# Thunderbots.net
KiCad netlist of a schematic drawn in Altium Designer
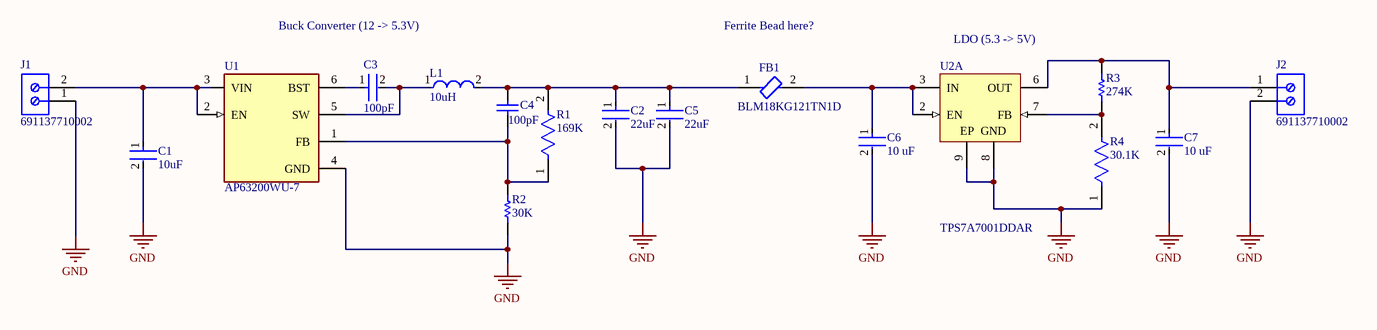
[diagram p0: Thunderbots.SchDoc]

(export (version "E")
  (design (tool "Eeschema 10.0.6"))
  (components
    (comp (ref "C1")
      (value "10uF")
      (footprint "FP-RDE3P1-MFG")
      (description "Ceramic Capacitor 10uF ±10% 50V X7S Radial")
      (fields (field (name "TOLERANCE") "10%"))
      (libsource (lib "Altium Content Vault") (part "02cd4be3c70576c341d710602a673aa"))
    )
    (comp (ref "C2")
      (value "22uF")
      (footprint "FP-RDEWK1-MFG")
      (description "CAP CER 22UF 50V X7S RADIAL")
      (fields (field (name "TOLERANCE") "20%"))
      (libsource (lib "Altium Content Vault") (part "02cd4be3c70576c341d710602a673aa"))
    )
    (comp (ref "C3")
      (value "100pF")
      (footprint "FP-C0402-BB-MFG")
      (description "C0402 0.10 μF X7R 10.00% 10 V")
      (fields (field (name "OCTOPART") "https://octopart.com/c0402c104k8ractu-kemet-106349"))
      (libsource (lib "Altium Content Vault") (part "b4654b650e69147ec39a6b967a45e02"))
    )
    (comp (ref "C4")
      (value "100pF")
      (footprint "CAPC2013X127X50NL20T25")
      (fields
        (field (name "PART NUMBER") "08052C101KAT2A")
        (field (name "MANUFACTURER") "AVX Interconnect / Elco")
      )
      (libsource (lib "Altium Content Vault") (part "CAP"))
    )
    (comp (ref "C5")
      (value "22uF")
      (footprint "FP-RDEWK1-MFG")
      (description "CAP CER 22UF 50V X7S RADIAL")
      (fields (field (name "TOLERANCE") "20%"))
      (libsource (lib "Altium Content Vault") (part "02cd4be3c70576c341d710602a673aa"))
    )
    (comp (ref "C6")
      (value "10 uF")
      (footprint "FP-RDE3P1-MFG")
      (description "Ceramic Capacitor 10uF ±10% 50V X7S Radial")
      (fields (field (name "TOLERANCE") "10%"))
      (libsource (lib "Altium Content Vault") (part "02cd4be3c70576c341d710602a673aa"))
    )
    (comp (ref "C7")
      (value "10 uF")
      (footprint "FP-CL05A106MP5NUNC-MFG")
      (description "CAP CER 10UF 10V X5R 0402")
      (fields
        (field (name "OCTOPART") "https://octopart.com/cl05a106mp5nunc-samsung-22457395")
        (field (name "TOLERANCE") "20%")
      )
      (libsource (lib "Altium Content Vault") (part "b4654b650e69147ec39a6b967a45e02"))
    )
    (comp (ref "FB1")
      (value "BLM18KG121TN1D")
      (footprint "FP-BLM18-0_15-t0_6-d1_2-IPC_A")
      (description "FERRITE BEAD 120 OHM 0603 1LN")
      (fields (field (name "TOLERANCE") "25%"))
      (libsource (lib "Altium Content Vault") (part "5f30dd21d616792df468990f7003faa"))
    )
    (comp (ref "J1")
      (value "691137710002")
      (footprint "691137710002")
      (libsource (lib "Altium Content Vault") (part "TBL - 1R - 02P - Screw"))
    )
    (comp (ref "J2")
      (value "691137710002")
      (footprint "691137710002")
      (libsource (lib "Altium Content Vault") (part "TBL - 1R - 02P - Screw"))
    )
    (comp (ref "L1")
      (value "10uH")
      (footprint "FP-NR6045-MFG")
      (description "Shielded Wirewound Inductor 10uH 20% 2.5A 61.1mΩ SMD")
      (fields (field (name "TOLERANCE") "20%"))
      (libsource (lib "Altium Content Vault") (part "725321dda6339637d4d059423bc1c3c"))
    )
    (comp (ref "R1")
      (value "169K")
      (footprint "FP-RMCF0603-IPC_A")
      (description "169kΩ ±1% 0.1W 0603 Thick Film Chip Resistor AEC-Q200 compliant")
      (fields (field (name "TOLERANCE") "1%"))
      (libsource (lib "Altium Content Vault") (part "1029c3af85768c4190bb7ad29bc67b5"))
    )
    (comp (ref "R2")
      (value "30K")
      (footprint "RESC1005X40X25LL05T05")
      (fields (field (name "PART NUMBER") "CRCW040230K0FKED") (field (name "MANUFACTURER") "Vishay Dale"))
      (libsource (lib "Altium Content Vault") (part "RES"))
    )
    (comp (ref "R3")
      (value "274K")
      (footprint "RESC1005X40X25ML05T05")
      (fields (field (name "MANUFACTURER") "Panasonic") (field (name "PART NUMBER") "ERJ-2RKF2743X"))
      (libsource (lib "Altium Content Vault") (part "RES"))
    )
    (comp (ref "R4")
      (value "30.1K")
      (footprint "FP-ERJ6EN-MFG")
      (fields (field (name "TOLERANCE") "1%"))
      (libsource (lib "Altium Content Vault") (part "1029c3af85768c4190bb7ad29bc67b5"))
    )
    (comp (ref "U1")
      (value "AP63200WU-7")
      (footprint "FP-TSOT26-MFG")
      (description "IC REG BUCK ADJUSTABLE 2A TSOT26")
      (fields
        (field (name "OCTOPART") "https://octopart.com/ap63200wu-7-diodes+inc.-98099548")
        (field (name "MANUFACTURER") "Diodes Inc.")
      )
      (libsource (lib "Altium Content Vault") (part "2ae3aed49e7ee94ca813948749813a1"))
    )
    (comp (ref "U2")
      (value "TPS7A7001DDAR")
      (footprint "DDA0008E_M")
      (fields (field (name "MANUFACTURER") "Texas Instruments"))
      (libsource (lib "Altium Content Vault") (part "TI-TPS7A7001DDA8-2875X2025TP"))
    )
  )
  (nets
    (net (code "1") (name "GND") (class "Default")
      (node (ref "C1") (pin "2") (pinfunction "2_2") (pintype "passive"))
      (node (ref "C2") (pin "2") (pinfunction "2_2") (pintype "passive"))
      (node (ref "C5") (pin "2") (pinfunction "2_2") (pintype "passive"))
      (node (ref "C6") (pin "2") (pinfunction "2_2") (pintype "passive"))
      (node (ref "C7") (pin "2") (pinfunction "2_2") (pintype "passive"))
      (node (ref "J1") (pin "1") (pinfunction "1_1") (pintype "passive"))
      (node (ref "J2") (pin "2") (pinfunction "2_2") (pintype "passive"))
      (node (ref "R2") (pin "1") (pinfunction "1_1") (pintype "passive"))
      (node (ref "R4") (pin "1") (pinfunction "1_1") (pintype "passive"))
      (node (ref "U1") (pin "4") (pinfunction "GND_4") (pintype "power_in"))
      (node (ref "U2") (pin "8") (pinfunction "GND_8") (pintype "power_in"))
      (node (ref "U2") (pin "9") (pinfunction "EP_9") (pintype "power_in"))
    )
    (net (code "2") (name "Net-(C2-Pad1)") (class "Default")
      (node (ref "C2") (pin "1") (pinfunction "1_1") (pintype "passive"))
      (node (ref "C4") (pin "2") (pinfunction "2_2") (pintype "passive"))
      (node (ref "C5") (pin "1") (pinfunction "1_1") (pintype "passive"))
      (node (ref "FB1") (pin "1") (pinfunction "1_1") (pintype "passive"))
      (node (ref "L1") (pin "2") (pinfunction "2_2") (pintype "passive"))
      (node (ref "R1") (pin "2") (pinfunction "2_2") (pintype "passive"))
    )
    (net (code "3") (name "Net-(U1-BST)") (class "Default")
      (node (ref "C3") (pin "1") (pinfunction "1_1") (pintype "passive"))
      (node (ref "U1") (pin "6") (pinfunction "BST_6") (pintype "passive"))
    )
    (net (code "4") (name "Net-(U1-EN)") (class "Default")
      (node (ref "C1") (pin "1") (pinfunction "1_1") (pintype "passive"))
      (node (ref "J1") (pin "2") (pinfunction "2_2") (pintype "passive"))
      (node (ref "U1") (pin "2") (pinfunction "EN_2") (pintype "input"))
      (node (ref "U1") (pin "3") (pinfunction "VIN_3") (pintype "power_in"))
    )
    (net (code "5") (name "Net-(U1-FB)") (class "Default")
      (node (ref "C4") (pin "1") (pinfunction "1_1") (pintype "passive"))
      (node (ref "R1") (pin "1") (pinfunction "1_1") (pintype "passive"))
      (node (ref "R2") (pin "2") (pinfunction "2_2") (pintype "passive"))
      (node (ref "U1") (pin "1") (pinfunction "FB_1") (pintype "passive"))
    )
    (net (code "6") (name "Net-(U1-SW)") (class "Default")
      (node (ref "C3") (pin "2") (pinfunction "2_2") (pintype "passive"))
      (node (ref "L1") (pin "1") (pinfunction "1_1") (pintype "passive"))
      (node (ref "U1") (pin "5") (pinfunction "SW_5") (pintype "passive"))
    )
    (net (code "7") (name "Net-(U2A-EN)") (class "Default")
      (node (ref "C6") (pin "1") (pinfunction "1_1") (pintype "passive"))
      (node (ref "FB1") (pin "2") (pinfunction "2_2") (pintype "passive"))
      (node (ref "U2") (pin "2") (pinfunction "EN_2") (pintype "input"))
      (node (ref "U2") (pin "3") (pinfunction "IN_3") (pintype "power_in"))
    )
    (net (code "8") (name "Net-(U2A-FB)") (class "Default")
      (node (ref "R3") (pin "2") (pinfunction "2_2") (pintype "passive"))
      (node (ref "R4") (pin "2") (pinfunction "2_2") (pintype "passive"))
      (node (ref "U2") (pin "7") (pinfunction "FB_7") (pintype "input"))
    )
    (net (code "9") (name "Net-(U2A-OUT)") (class "Default")
      (node (ref "C7") (pin "1") (pinfunction "1_1") (pintype "passive"))
      (node (ref "J2") (pin "1") (pinfunction "1_1") (pintype "passive"))
      (node (ref "R3") (pin "1") (pinfunction "1_1") (pintype "passive"))
      (node (ref "U2") (pin "6") (pinfunction "OUT_6") (pintype "power_in"))
    )
  )
)
